# pulser_one_pad.net
KiCad netlist of a schematic drawn in Altium Designer
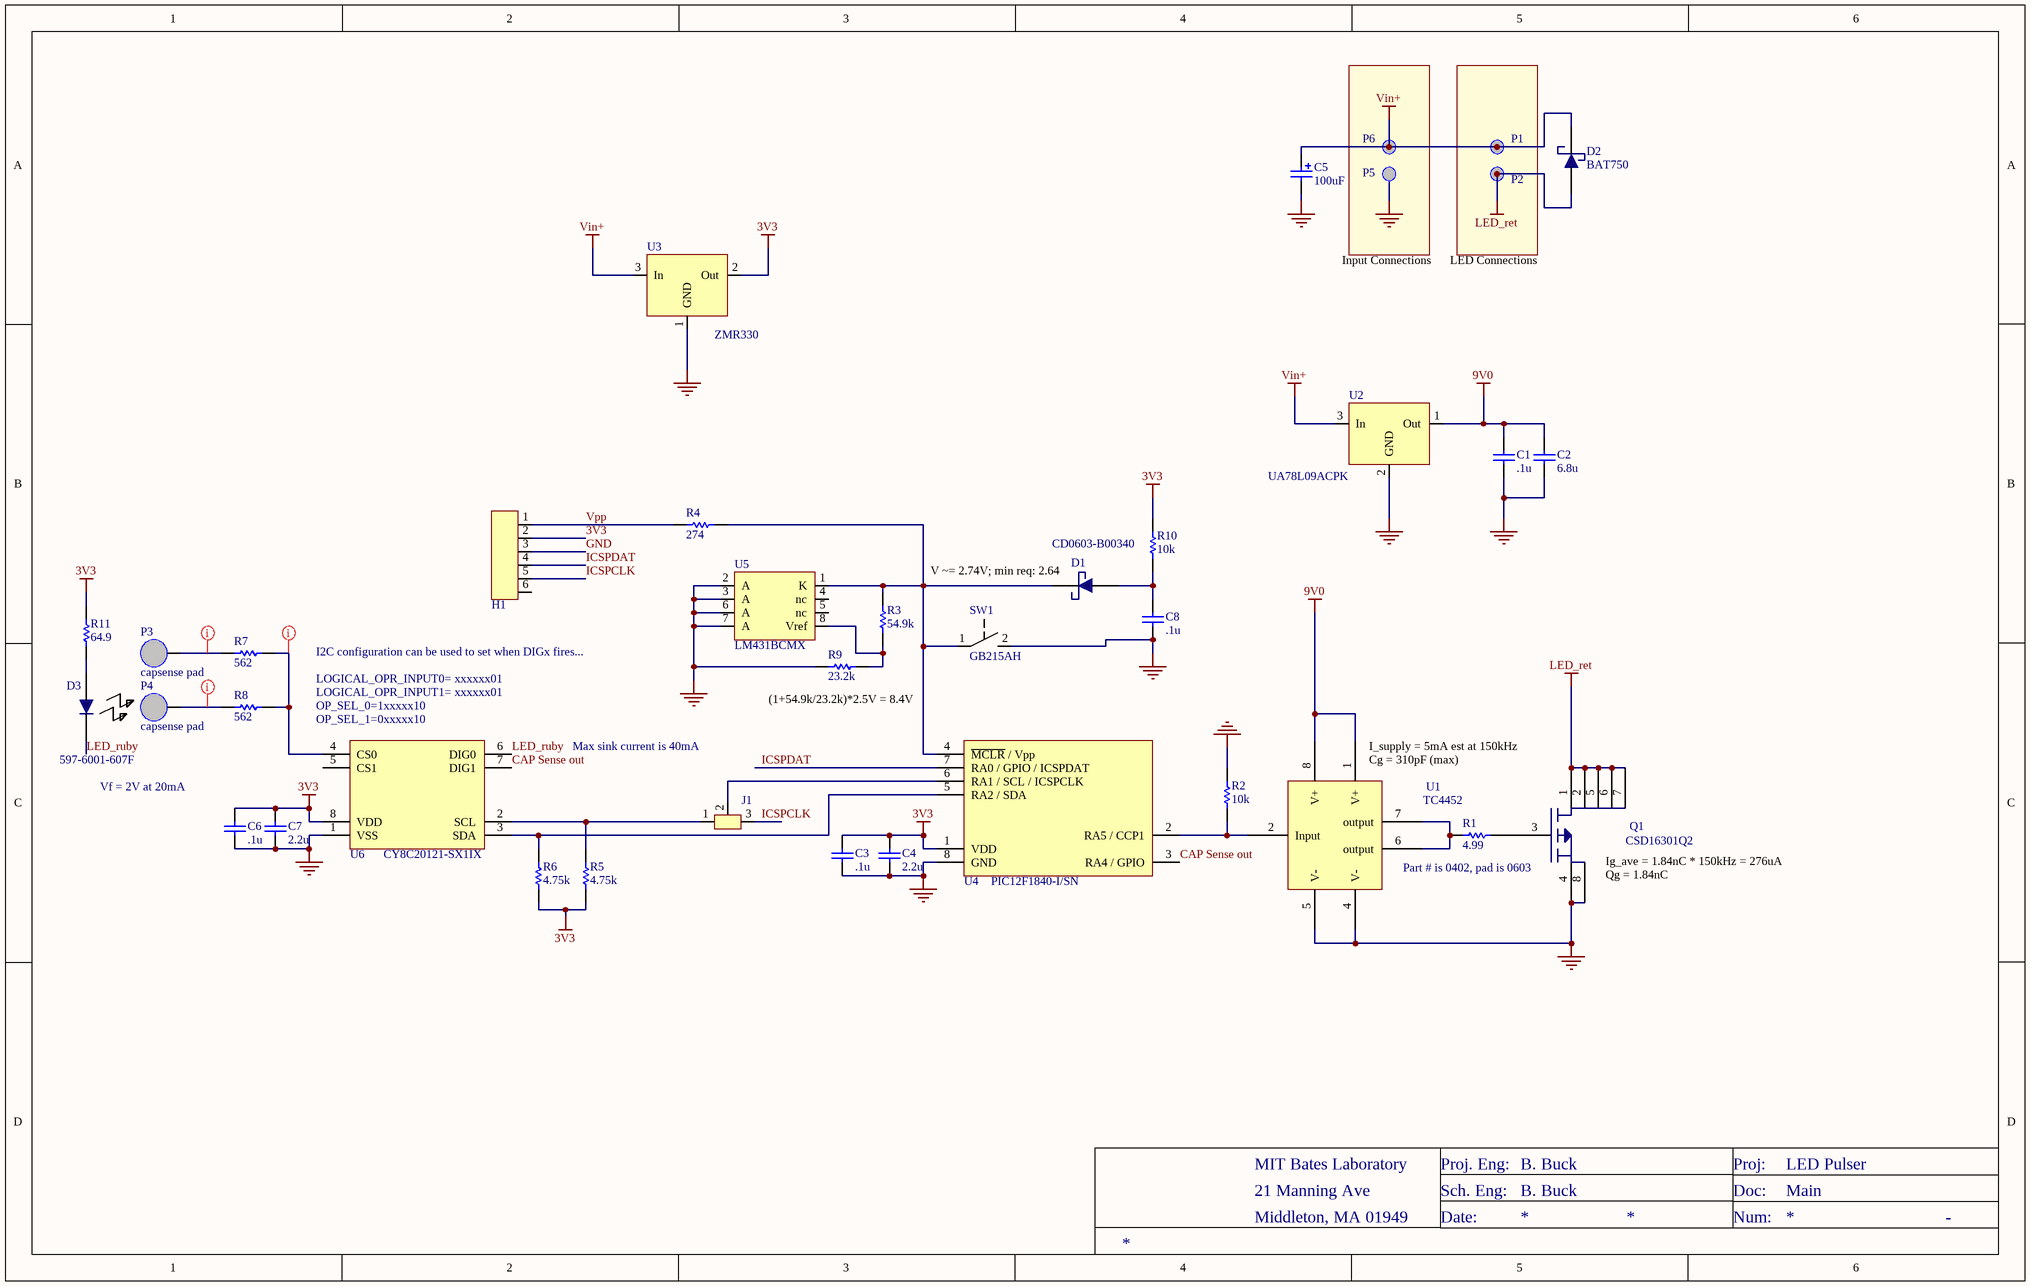
[diagram p0: pulser one pad.SchDoc]

(export (version "E")
  (design (tool "Eeschema 10.0.6"))
  (components
    (comp (ref "C1")
      (value ".1u")
      (footprint "SMD0603")
      (description "Capacitor")
      (fields
        (field (name "PARTNUMBER") "250R14W104KV4T")
        (field (name "MANUFACTURER") "Johanson Dielectrics")
      )
      (libsource (lib "pulser") (part "Cap"))
    )
    (comp (ref "C2")
      (value "6.8u")
      (footprint "SMD1812")
      (description "Capacitor")
      (fields (field (name "PARTNUMBER") "C4532X5R1H685K250KA") (field (name "MANUFACTURER") "TDK"))
      (libsource (lib "pulser") (part "Cap"))
    )
    (comp (ref "C3")
      (value ".1u")
      (footprint "SMD0603")
      (description "Capacitor")
      (fields
        (field (name "PARTNUMBER") "250R14W104KV4T")
        (field (name "MANUFACTURER") "Johanson Dielectrics")
      )
      (libsource (lib "pulser") (part "Cap"))
    )
    (comp (ref "C4")
      (value "2.2u")
      (footprint "SMD0603")
      (description "Capacitor")
      (fields (field (name "PARTNUMBER") "C1608X5R1V225K080AC") (field (name "MANUFACTURER") "TDK"))
      (libsource (lib "pulser") (part "Cap"))
    )
    (comp (ref "C5")
      (value "100uF")
      (footprint "Tant Cap Size D")
      (description "Capacitor")
      (fields (field (name "PARTNUMBER") "T495X476K035ATE300") (field (name "MANUFACTURER") "Kemet"))
      (libsource (lib "pulser") (part "CapPol"))
    )
    (comp (ref "C6")
      (value ".1u")
      (footprint "SMD0603")
      (description "Capacitor")
      (fields
        (field (name "PARTNUMBER") "250R14W104KV4T")
        (field (name "MANUFACTURER") "Johanson Dielectrics")
      )
      (libsource (lib "pulser") (part "Cap"))
    )
    (comp (ref "C7")
      (value "2.2u")
      (footprint "SMD0603")
      (description "Capacitor")
      (fields (field (name "PARTNUMBER") "C1608X5R1V225K080AC") (field (name "MANUFACTURER") "TDK"))
      (libsource (lib "pulser") (part "Cap"))
    )
    (comp (ref "C8")
      (value ".1u")
      (footprint "SMD0603")
      (description "Capacitor")
      (fields
        (field (name "PARTNUMBER") "250R14W104KV4T")
        (field (name "MANUFACTURER") "Johanson Dielectrics")
      )
      (libsource (lib "pulser") (part "Cap"))
    )
    (comp (ref "D1")
      (value "CD0603-B00340")
      (footprint "SMD0603 Polarized")
      (description "Schottky Diode")
      (fields (field (name "MANUFACTURER") "Bourns"))
      (libsource (lib "pulser") (part "CD0603-B00340"))
    )
    (comp (ref "D2")
      (value "BAT750")
      (footprint "SOT23 - Diodes")
      (description "Schottky Diode high current")
      (fields (field (name "MANUFACTURER") "Diodes / Zetex"))
      (libsource (lib "pulser") (part "BAT750"))
    )
    (comp (ref "D3")
      (value "597-6001-607F")
      (footprint "SMD1206 Rev Mount LED")
      (description "Reverse Mount 1206 LED")
      (fields (field (name "MANUFACTURER") "Dialight"))
      (libsource (lib "pulser") (part "1206 reverse mount LED"))
    )
    (comp (ref "H1")
      (value "6 pin header")
      (footprint "6 pin header")
      (description "6 Pin Header")
      (libsource (lib "pulser") (part "6 pin header"))
    )
    (comp (ref "J1")
      (value "jumper")
      (footprint "3 PIN HEADER")
      (description "Three Pin Jumper")
      (libsource (lib "pulser") (part "jumper"))
    )
    (comp (ref "P1")
      (value "16AWG Solder Point")
      (footprint "16 AWG Solder Point")
      (libsource (lib "pulser") (part "16AWG Solder Point"))
    )
    (comp (ref "P2")
      (value "16AWG Solder Point")
      (footprint "16 AWG Solder Point")
      (libsource (lib "pulser") (part "16AWG Solder Point"))
    )
    (comp (ref "P3")
      (value "capsense pad")
      (footprint "CAPSENSE RUBY")
      (description "circular capsense pad")
      (libsource (lib "pulser") (part "capsense pad 1"))
    )
    (comp (ref "P4")
      (value "capsense pad")
      (footprint "capsense ruby 5.9mm")
      (description "circular capsense pad")
      (libsource (lib "pulser") (part "capsense pad 1"))
    )
    (comp (ref "P5")
      (value "16AWG Solder Point")
      (footprint "16 AWG Solder Point")
      (libsource (lib "pulser") (part "16AWG Solder Point"))
    )
    (comp (ref "P6")
      (value "16AWG Solder Point")
      (footprint "16 AWG Solder Point")
      (libsource (lib "pulser") (part "16AWG Solder Point"))
    )
    (comp (ref "Q1")
      (value "CSD16301Q2")
      (footprint "CSD16301Q2")
      (description "N Ch. MOSFET")
      (fields (field (name "MANUFACTURER") "Texas Instruments"))
      (libsource (lib "pulser") (part "CSD16301Q2"))
    )
    (comp (ref "R1")
      (value "4.99")
      (footprint "SMD0603")
      (description "Resistor")
      (fields (field (name "PARTNUMBER") "CRCW04024R99FK") (field (name "MANUFACTURER") "Vishay / Dale"))
      (libsource (lib "pulser") (part "Res"))
    )
    (comp (ref "R2")
      (value "10k")
      (footprint "SMD0603")
      (description "Resistor")
      (fields (field (name "PARTNUMBER") "CRCW060310K0FK") (field (name "MANUFACTURER") "Vishay / Dale"))
      (libsource (lib "pulser") (part "Res"))
    )
    (comp (ref "R3")
      (value "54.9k")
      (footprint "SMD0603")
      (description "Resistor")
      (fields (field (name "PARTNUMBER") "CRCW060354K9FK") (field (name "MANUFACTURER") "Vishay / Dale"))
      (libsource (lib "pulser") (part "Res"))
    )
    (comp (ref "R4")
      (value "274")
      (footprint "SMD0603")
      (description "Resistor")
      (fields (field (name "PARTNUMBER") "CRCW0603274RFK") (field (name "MANUFACTURER") "Vishay / Dale"))
      (libsource (lib "pulser") (part "Res"))
    )
    (comp (ref "R5")
      (value "4.75k")
      (footprint "SMD0603")
      (description "Resistor")
      (fields (field (name "PARTNUMBER") "CRCW06034K75FK") (field (name "MANUFACTURER") "Vishay / Dale"))
      (libsource (lib "pulser") (part "Res"))
    )
    (comp (ref "R6")
      (value "4.75k")
      (footprint "SMD0603")
      (description "Resistor")
      (fields (field (name "PARTNUMBER") "CRCW06034K75FK") (field (name "MANUFACTURER") "Vishay / Dale"))
      (libsource (lib "pulser") (part "Res"))
    )
    (comp (ref "R7")
      (value "562")
      (footprint "SMD0603")
      (description "Resistor")
      (fields (field (name "PARTNUMBER") "CRCW0603562RFK") (field (name "MANUFACTURER") "Vishay / Dale"))
      (libsource (lib "pulser") (part "Res"))
    )
    (comp (ref "R8")
      (value "562")
      (footprint "SMD0603")
      (description "Resistor")
      (fields (field (name "PARTNUMBER") "CRCW0603562RFK") (field (name "MANUFACTURER") "Vishay / Dale"))
      (libsource (lib "pulser") (part "Res"))
    )
    (comp (ref "R9")
      (value "23.2k")
      (footprint "SMD0603")
      (description "Resistor")
      (fields (field (name "PARTNUMBER") "CRCW060323K2FK") (field (name "MANUFACTURER") "Vishay / Dale"))
      (libsource (lib "pulser") (part "Res"))
    )
    (comp (ref "R10")
      (value "10k")
      (footprint "SMD0603")
      (description "Resistor")
      (fields (field (name "PARTNUMBER") "CRCW060310K0FK") (field (name "MANUFACTURER") "Vishay / Dale"))
      (libsource (lib "pulser") (part "Res"))
    )
    (comp (ref "R11")
      (value "64.9")
      (footprint "SMD0603")
      (description "Resistor")
      (fields (field (name "PARTNUMBER") "CRCW060364R9FK") (field (name "MANUFACTURER") "Vishay / Dale"))
      (libsource (lib "pulser") (part "Res"))
    )
    (comp (ref "SW1")
      (value "GB215AH")
      (footprint "GB215AH")
      (description "SPST Normally Open Switch")
      (fields (field (name "MANUFACTURER") "NKK Switches"))
      (libsource (lib "pulser") (part "GB215AH"))
    )
    (comp (ref "U1")
      (value "TC4452")
      (footprint "8 PIN SOIC")
      (description "MOSFET Gate Driver, Low Side, Non Inverting 13A max")
      (fields (field (name "MANUFACTURER") "Microchip") (field (name "PARTNUMBER") "TC4452VOA"))
      (libsource (lib "pulser") (part "TC4452"))
    )
    (comp (ref "U2")
      (value "UA78L09ACPK")
      (footprint "SOT89-150P350X160-3N")
      (description "9V linear fixed regulator, TI Part")
      (fields (field (name "MANUFACTURER") "Texas Instruments"))
      (libsource (lib "pulser") (part "UA78L09ACPK"))
    )
    (comp (ref "U3")
      (value "ZMR330")
      (footprint "SOT23 - Diodes")
      (description "Diodes 3.3V LDO regulator, 50mA")
      (fields (field (name "MANUFACTURER") "Diodes") (field (name "PARTNUMBER") "ZMR330FTA"))
      (libsource (lib "pulser") (part "ZMR330"))
    )
    (comp (ref "U4")
      (value "PIC12F1840-I/SN")
      (footprint "8 PIN SOIC")
      (description "8 Bit RISC uController")
      (fields (field (name "MANUFACTURER") "Microchip"))
      (libsource (lib "pulser") (part "PIC12F1840-I/SN"))
    )
    (comp (ref "U5")
      (value "LM431BCMX")
      (footprint "8 PIN SOIC")
      (description "Adjustable Voltage Reference")
      (fields (field (name "MANUFACTURER") "Fairchild Semiconductor") (field (name "PARTNUMBER") "LM431ACMX"))
      (libsource (lib "pulser") (part "LM431BCMX"))
    )
    (comp (ref "U6")
      (value "CY8C20121-SX1I")
      (footprint "8 PIN SOIC")
      (description "Capsense Module, 2 button")
      (fields (field (name "PARTNUMBER") "CY8C20121-SX1IX") (field (name "MANUFACTURER") "Cypress"))
      (libsource (lib "pulser") (part "CY8C20121-SX1I"))
    )
  )
  (nets
    (net (code "1") (name "/CAP Sense out") (class "Default")
      (node (ref "U4") (pin "3") (pinfunction "RA4_/_GPIO_3") (pintype "passive"))
      (node (ref "U6") (pin "7") (pinfunction "DIG1_7") (pintype "passive"))
    )
    (net (code "2") (name "/ICSPCLK") (class "Default")
      (node (ref "H1") (pin "5") (pinfunction "5_5") (pintype "passive"))
      (node (ref "J1") (pin "3") (pinfunction "3_3") (pintype "passive"))
    )
    (net (code "3") (name "/ICSPDAT") (class "Default")
      (node (ref "H1") (pin "4") (pinfunction "4_4") (pintype "passive"))
      (node (ref "U4") (pin "7") (pinfunction "RA0_/_GPIO_/_ICSPDAT_7") (pintype "passive"))
    )
    (net (code "4") (name "/LED_ruby") (class "Default")
      (node (ref "D3") (pin "K") (pinfunction "K_K") (pintype "passive"))
      (node (ref "U6") (pin "6") (pinfunction "DIG0_6") (pintype "passive"))
    )
    (net (code "5") (name "/Vpp") (class "Default")
      (node (ref "H1") (pin "1") (pinfunction "1_1") (pintype "passive"))
      (node (ref "R4") (pin "2") (pinfunction "2_2") (pintype "passive"))
    )
    (net (code "6") (name "3V3") (class "Default")
      (node (ref "C3") (pin "2") (pinfunction "2_2") (pintype "passive"))
      (node (ref "C4") (pin "2") (pinfunction "2_2") (pintype "passive"))
      (node (ref "C6") (pin "2") (pinfunction "2_2") (pintype "passive"))
      (node (ref "C7") (pin "2") (pinfunction "2_2") (pintype "passive"))
      (node (ref "H1") (pin "2") (pinfunction "2_2") (pintype "passive"))
      (node (ref "R10") (pin "1") (pinfunction "1_1") (pintype "passive"))
      (node (ref "R11") (pin "2") (pinfunction "2_2") (pintype "passive"))
      (node (ref "R5") (pin "2") (pinfunction "2_2") (pintype "passive"))
      (node (ref "R6") (pin "2") (pinfunction "2_2") (pintype "passive"))
      (node (ref "U3") (pin "2") (pinfunction "Out_2") (pintype "passive"))
      (node (ref "U4") (pin "1") (pinfunction "VDD_1") (pintype "passive"))
      (node (ref "U6") (pin "8") (pinfunction "VDD_8") (pintype "passive"))
    )
    (net (code "7") (name "9V0") (class "Default")
      (node (ref "C1") (pin "2") (pinfunction "2_2") (pintype "passive"))
      (node (ref "C2") (pin "2") (pinfunction "2_2") (pintype "passive"))
      (node (ref "U1") (pin "1") (pinfunction "V+_1") (pintype "passive"))
      (node (ref "U1") (pin "8") (pinfunction "V+_8") (pintype "passive"))
      (node (ref "U2") (pin "1") (pinfunction "Out_1") (pintype "passive"))
    )
    (net (code "8") (name "GND") (class "Default")
      (node (ref "C1") (pin "1") (pinfunction "1_1") (pintype "passive"))
      (node (ref "C2") (pin "1") (pinfunction "1_1") (pintype "passive"))
      (node (ref "C3") (pin "1") (pinfunction "1_1") (pintype "passive"))
      (node (ref "C4") (pin "1") (pinfunction "1_1") (pintype "passive"))
      (node (ref "C5") (pin "2") (pinfunction "2_2") (pintype "passive"))
      (node (ref "C6") (pin "1") (pinfunction "1_1") (pintype "passive"))
      (node (ref "C7") (pin "1") (pinfunction "1_1") (pintype "passive"))
      (node (ref "C8") (pin "1") (pinfunction "1_1") (pintype "passive"))
      (node (ref "H1") (pin "3") (pinfunction "3_3") (pintype "passive"))
      (node (ref "P5") (pin "1") (pinfunction "1_1") (pintype "passive"))
      (node (ref "Q1") (pin "4") (pintype "passive"))
      (node (ref "Q1") (pin "8") (pintype "passive"))
      (node (ref "R2") (pin "2") (pinfunction "2_2") (pintype "passive"))
      (node (ref "R9") (pin "2") (pinfunction "2_2") (pintype "passive"))
      (node (ref "SW1") (pin "2") (pinfunction "2_2") (pintype "passive"))
      (node (ref "U1") (pin "4") (pinfunction "V-_4") (pintype "passive"))
      (node (ref "U1") (pin "5") (pinfunction "V-_5") (pintype "passive"))
      (node (ref "U2") (pin "2") (pinfunction "GND_2") (pintype "passive"))
      (node (ref "U3") (pin "1") (pinfunction "GND_1") (pintype "passive"))
      (node (ref "U4") (pin "8") (pinfunction "GND_8") (pintype "passive"))
      (node (ref "U5") (pin "2") (pinfunction "A_2") (pintype "passive"))
      (node (ref "U5") (pin "3") (pinfunction "A_3") (pintype "passive"))
      (node (ref "U5") (pin "6") (pinfunction "A_6") (pintype "passive"))
      (node (ref "U5") (pin "7") (pinfunction "A_7") (pintype "passive"))
      (node (ref "U6") (pin "1") (pinfunction "VSS_1") (pintype "passive"))
    )
    (net (code "9") (name "LED_ret") (class "Default")
      (node (ref "D2") (pin "2") (pinfunction "A_2") (pintype "passive"))
      (node (ref "P2") (pin "1") (pinfunction "1_1") (pintype "passive"))
      (node (ref "Q1") (pin "1") (pintype "passive"))
      (node (ref "Q1") (pin "2") (pintype "passive"))
      (node (ref "Q1") (pin "5") (pintype "passive"))
      (node (ref "Q1") (pin "6") (pintype "passive"))
      (node (ref "Q1") (pin "7") (pintype "passive"))
    )
    (net (code "10") (name "Net-(D1-A)") (class "Default")
      (node (ref "C8") (pin "2") (pinfunction "2_2") (pintype "passive"))
      (node (ref "D1") (pin "2") (pinfunction "A_2") (pintype "passive"))
      (node (ref "R10") (pin "2") (pinfunction "2_2") (pintype "passive"))
    )
    (net (code "11") (name "Net-(D1-K)") (class "Default")
      (node (ref "D1") (pin "1") (pinfunction "K_1") (pintype "passive"))
      (node (ref "R3") (pin "2") (pinfunction "2_2") (pintype "passive"))
      (node (ref "R4") (pin "1") (pinfunction "1_1") (pintype "passive"))
      (node (ref "SW1") (pin "1") (pinfunction "1_1") (pintype "passive"))
      (node (ref "U4") (pin "4") (pinfunction "~{MCLR}_/_Vpp_4") (pintype "passive"))
      (node (ref "U5") (pin "1") (pinfunction "K_1") (pintype "passive"))
    )
    (net (code "12") (name "Net-(D3-PadA)") (class "Default")
      (node (ref "D3") (pin "A") (pinfunction "A_A") (pintype "passive"))
      (node (ref "R11") (pin "1") (pinfunction "1_1") (pintype "passive"))
    )
    (net (code "13") (name "Net-(P3-Pad1)") (class "Default")
      (node (ref "P3") (pin "1") (pintype "passive"))
      (node (ref "R7") (pin "2") (pinfunction "2_2") (pintype "passive"))
    )
    (net (code "14") (name "Net-(P4-Pad1)") (class "Default")
      (node (ref "P4") (pin "1") (pintype "passive"))
      (node (ref "R8") (pin "2") (pinfunction "2_2") (pintype "passive"))
    )
    (net (code "15") (name "Net-(Q1-Pad3)") (class "Default")
      (node (ref "Q1") (pin "3") (pintype "passive"))
      (node (ref "R1") (pin "1") (pinfunction "1_1") (pintype "passive"))
    )
    (net (code "16") (name "Net-(R1-Pad2)") (class "Default")
      (node (ref "R1") (pin "2") (pinfunction "2_2") (pintype "passive"))
      (node (ref "U1") (pin "6") (pinfunction "output_6") (pintype "passive"))
      (node (ref "U1") (pin "7") (pinfunction "output_7") (pintype "passive"))
    )
    (net (code "17") (name "Net-(U1-Input)") (class "Default")
      (node (ref "R2") (pin "1") (pinfunction "1_1") (pintype "passive"))
      (node (ref "U1") (pin "2") (pinfunction "Input_2") (pintype "passive"))
      (node (ref "U4") (pin "2") (pinfunction "RA5_/_CCP1_2") (pintype "passive"))
    )
    (net (code "18") (name "Net-(U4-RA1_{slash}_SCL_{slash}_ICSPCLK)") (class "Default")
      (node (ref "J1") (pin "2") (pinfunction "2_2") (pintype "passive"))
      (node (ref "U4") (pin "6") (pinfunction "RA1_/_SCL_/_ICSPCLK_6") (pintype "passive"))
    )
    (net (code "19") (name "Net-(U4-RA2_{slash}_SDA)") (class "Default")
      (node (ref "R6") (pin "1") (pinfunction "1_1") (pintype "passive"))
      (node (ref "U4") (pin "5") (pinfunction "RA2_/_SDA_5") (pintype "passive"))
      (node (ref "U6") (pin "3") (pinfunction "SDA_3") (pintype "passive"))
    )
    (net (code "20") (name "Net-(U5-Vref)") (class "Default")
      (node (ref "R3") (pin "1") (pinfunction "1_1") (pintype "passive"))
      (node (ref "R9") (pin "1") (pinfunction "1_1") (pintype "passive"))
      (node (ref "U5") (pin "8") (pinfunction "Vref_8") (pintype "passive"))
    )
    (net (code "21") (name "Net-(U6-CS0)") (class "Default")
      (node (ref "R7") (pin "1") (pinfunction "1_1") (pintype "passive"))
      (node (ref "R8") (pin "1") (pinfunction "1_1") (pintype "passive"))
      (node (ref "U6") (pin "4") (pinfunction "CS0_4") (pintype "passive"))
    )
    (net (code "22") (name "Net-(U6-SCL)") (class "Default")
      (node (ref "J1") (pin "1") (pinfunction "1_1") (pintype "passive"))
      (node (ref "R5") (pin "1") (pinfunction "1_1") (pintype "passive"))
      (node (ref "U6") (pin "2") (pinfunction "SCL_2") (pintype "passive"))
    )
    (net (code "23") (name "Vin+") (class "Default")
      (node (ref "C5") (pin "1") (pinfunction "1_1") (pintype "passive"))
      (node (ref "D2") (pin "1") (pinfunction "K_1") (pintype "passive"))
      (node (ref "P1") (pin "1") (pinfunction "1_1") (pintype "passive"))
      (node (ref "P6") (pin "1") (pinfunction "1_1") (pintype "passive"))
      (node (ref "U2") (pin "3") (pinfunction "In_3") (pintype "passive"))
      (node (ref "U3") (pin "3") (pinfunction "In_3") (pintype "passive"))
    )
    (net (code "24") (name "unconnected-(H1-Pad6)") (class "Default")
      (node (ref "H1") (pin "6") (pinfunction "6_6") (pintype "passive"))
    )
    (net (code "25") (name "unconnected-(U5-nc-Pad4)") (class "Default")
      (node (ref "U5") (pin "4") (pinfunction "nc_4") (pintype "passive"))
    )
    (net (code "26") (name "unconnected-(U5-nc-Pad5)") (class "Default")
      (node (ref "U5") (pin "5") (pinfunction "nc_5") (pintype "passive"))
    )
    (net (code "27") (name "unconnected-(U6-CS1-Pad5)") (class "Default")
      (node (ref "U6") (pin "5") (pinfunction "CS1_5") (pintype "passive"))
    )
  )
)
